# PWR_AFE.net
KiCad netlist of a schematic drawn in Altium Designer
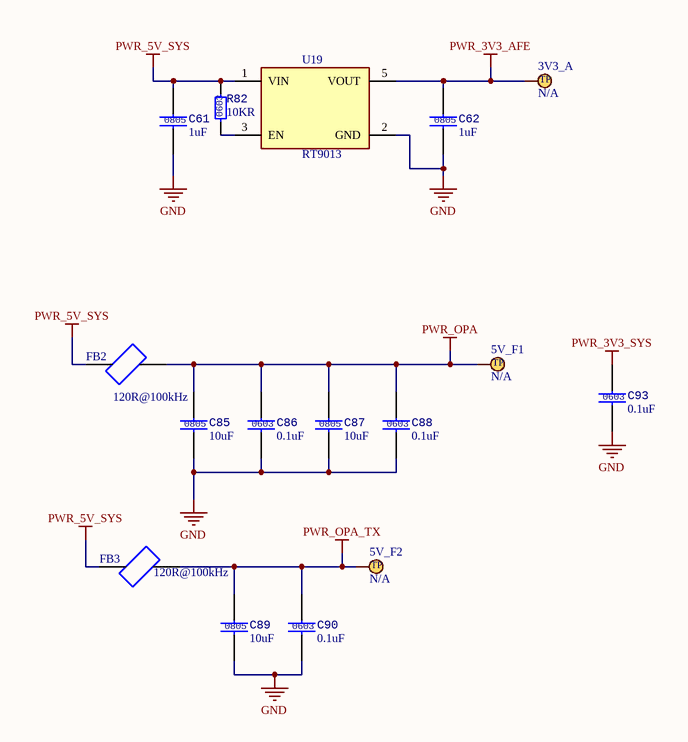
[diagram p0: PWR_AFE.SchDoc]

(export (version "E")
  (design (tool "Eeschema 10.0.6"))
  (components
    (comp (ref "3V3_A")
      (value "N/A")
      (footprint "Test_point")
      (fields (field (name "Comment") "TEST_POINT"))
      (libsource (lib "Database_Libs1") (part "Test_point"))
    )
    (comp (ref "5V_F1")
      (value "N/A")
      (footprint "Test_point")
      (fields (field (name "Comment") "TEST_POINT"))
      (libsource (lib "Database_Libs1") (part "Test_point"))
    )
    (comp (ref "5V_F2")
      (value "N/A")
      (footprint "Test_point")
      (fields (field (name "Comment") "TEST_POINT"))
      (libsource (lib "Database_Libs1") (part "Test_point"))
    )
    (comp (ref "C61")
      (value "1uF")
      (footprint "CAPCER 0805 SMD")
      (description "CAPACITOR SMD 1uF 16V 10% 0805")
      (fields (field (name "SIZE") "0805") (field (name "TOLERANCE") "10%"))
      (libsource (lib "Database_Libs1") (part "CAPACITOR"))
    )
    (comp (ref "C62")
      (value "1uF")
      (footprint "CAPCER 0805 SMD")
      (description "CAPACITOR SMD 1uF 16V 10% 0805")
      (fields (field (name "SIZE") "0805") (field (name "TOLERANCE") "10%"))
      (libsource (lib "Database_Libs1") (part "CAPACITOR"))
    )
    (comp (ref "C85")
      (value "10uF")
      (footprint "CAPCER 0805 SMD")
      (description "CAPACITOR SMD 10uF 25V 10% 0805")
      (fields (field (name "SIZE") "0805") (field (name "TOLERANCE") "10%"))
      (libsource (lib "Database_Libs1") (part "CAPACITOR"))
    )
    (comp (ref "C86")
      (value "0.1uF")
      (footprint "CAPCER 0805 SMD")
      (description "CAPACITOR SMD 0.1uF 50V 10% 0603")
      (fields (field (name "SIZE") "0603") (field (name "TOLERANCE") "10%"))
      (libsource (lib "Database_Libs1") (part "CAPACITOR"))
    )
    (comp (ref "C87")
      (value "10uF")
      (footprint "CAPCER 0805 SMD")
      (description "CAPACITOR SMD 10uF 25V 10% 0805")
      (fields (field (name "SIZE") "0805") (field (name "TOLERANCE") "10%"))
      (libsource (lib "Database_Libs1") (part "CAPACITOR"))
    )
    (comp (ref "C88")
      (value "0.1uF")
      (footprint "CAPCER 0805 SMD")
      (description "CAPACITOR SMD 0.1uF 50V 10% 0603")
      (fields (field (name "SIZE") "0603") (field (name "TOLERANCE") "10%"))
      (libsource (lib "Database_Libs1") (part "CAPACITOR"))
    )
    (comp (ref "C89")
      (value "10uF")
      (footprint "CAPCER 0805 SMD")
      (description "CAPACITOR SMD 10uF 25V 10% 0805")
      (fields (field (name "SIZE") "0805") (field (name "TOLERANCE") "10%"))
      (libsource (lib "Database_Libs1") (part "CAPACITOR"))
    )
    (comp (ref "C90")
      (value "0.1uF")
      (footprint "CAPCER 0805 SMD")
      (description "CAPACITOR SMD 0.1uF 50V 10% 0603")
      (fields (field (name "SIZE") "0603") (field (name "TOLERANCE") "10%"))
      (libsource (lib "Database_Libs1") (part "CAPACITOR"))
    )
    (comp (ref "C93")
      (value "0.1uF")
      (footprint "CAPCER 0805 SMD")
      (description "CAPACITOR SMD 0.1uF 50V 10% 0603")
      (fields (field (name "SIZE") "0603") (field (name "TOLERANCE") "10%"))
      (libsource (lib "Database_Libs1") (part "CAPACITOR"))
    )
    (comp (ref "FB2")
      (value "120R@100kHz")
      (footprint "FB 0805")
      (description "CBW201209U121T Ferrite Beads 2A 120 Ohm 0805")
      (libsource (lib "Database_Libs1") (part "FB"))
    )
    (comp (ref "FB3")
      (value "120R@100kHz")
      (footprint "FB 0805")
      (description "CBW201209U121T Ferrite Beads 2A 120 Ohm 0805")
      (libsource (lib "Database_Libs1") (part "FB"))
    )
    (comp (ref "R82")
      (value "10KR")
      (footprint "RESC 0603(1608) SMD")
      (description "RESISTOR SMD 10KR OHM 1% 100mW 0603")
      (fields (field (name "SIZE") "0603") (field (name "TOLERANCE") "1%"))
      (libsource (lib "Database_Libs1") (part "RESISTOR"))
    )
    (comp (ref "U19")
      (value "RT9013")
      (footprint "SOT-23-5")
      (description "IC REG LINEAR 3.3V 500MA SOT23-5")
      (libsource (lib "Database_Libs1") (part "RT9013"))
    )
  )
  (nets
    (net (code "1") (name "GND") (class "Default")
      (node (ref "C61") (pin "2") (pinfunction "2_2") (pintype "passive"))
      (node (ref "C62") (pin "2") (pinfunction "2_2") (pintype "passive"))
      (node (ref "C85") (pin "2") (pinfunction "2_2") (pintype "passive"))
      (node (ref "C86") (pin "2") (pinfunction "2_2") (pintype "passive"))
      (node (ref "C87") (pin "2") (pinfunction "2_2") (pintype "passive"))
      (node (ref "C88") (pin "2") (pinfunction "2_2") (pintype "passive"))
      (node (ref "C89") (pin "2") (pinfunction "2_2") (pintype "passive"))
      (node (ref "C90") (pin "2") (pinfunction "2_2") (pintype "passive"))
      (node (ref "C93") (pin "2") (pinfunction "2_2") (pintype "passive"))
      (node (ref "U19") (pin "2") (pinfunction "GND_2") (pintype "power_in"))
    )
    (net (code "2") (name "Net-(U19-EN)") (class "Default")
      (node (ref "R82") (pin "1") (pinfunction "1_1") (pintype "passive"))
      (node (ref "U19") (pin "3") (pinfunction "EN_3") (pintype "passive"))
    )
    (net (code "3") (name "PWR_3V3_AFE") (class "Default")
      (node (ref "3V3_A") (pin "1") (pinfunction "1_1") (pintype "passive"))
      (node (ref "C62") (pin "1") (pinfunction "1_1") (pintype "passive"))
      (node (ref "U19") (pin "5") (pinfunction "VOUT_5") (pintype "passive"))
    )
    (net (code "4") (name "PWR_3V3_SYS") (class "Default")
      (node (ref "C93") (pin "1") (pinfunction "1_1") (pintype "passive"))
    )
    (net (code "5") (name "PWR_5V_SYS") (class "Default")
      (node (ref "C61") (pin "1") (pinfunction "1_1") (pintype "passive"))
      (node (ref "FB2") (pin "1") (pinfunction "1_1") (pintype "passive"))
      (node (ref "FB3") (pin "1") (pinfunction "1_1") (pintype "passive"))
      (node (ref "R82") (pin "2") (pinfunction "2_2") (pintype "passive"))
      (node (ref "U19") (pin "1") (pinfunction "VIN_1") (pintype "power_in"))
    )
    (net (code "6") (name "PWR_OPA") (class "Default")
      (node (ref "5V_F1") (pin "1") (pinfunction "1_1") (pintype "passive"))
      (node (ref "C85") (pin "1") (pinfunction "1_1") (pintype "passive"))
      (node (ref "C86") (pin "1") (pinfunction "1_1") (pintype "passive"))
      (node (ref "C87") (pin "1") (pinfunction "1_1") (pintype "passive"))
      (node (ref "C88") (pin "1") (pinfunction "1_1") (pintype "passive"))
      (node (ref "FB2") (pin "2") (pinfunction "2_2") (pintype "passive"))
    )
    (net (code "7") (name "PWR_OPA_TX") (class "Default")
      (node (ref "5V_F2") (pin "1") (pinfunction "1_1") (pintype "passive"))
      (node (ref "C89") (pin "1") (pinfunction "1_1") (pintype "passive"))
      (node (ref "C90") (pin "1") (pinfunction "1_1") (pintype "passive"))
      (node (ref "FB3") (pin "2") (pinfunction "2_2") (pintype "passive"))
    )
  )
)
